# Endstops.net
KiCad netlist of a schematic drawn in Altium Designer
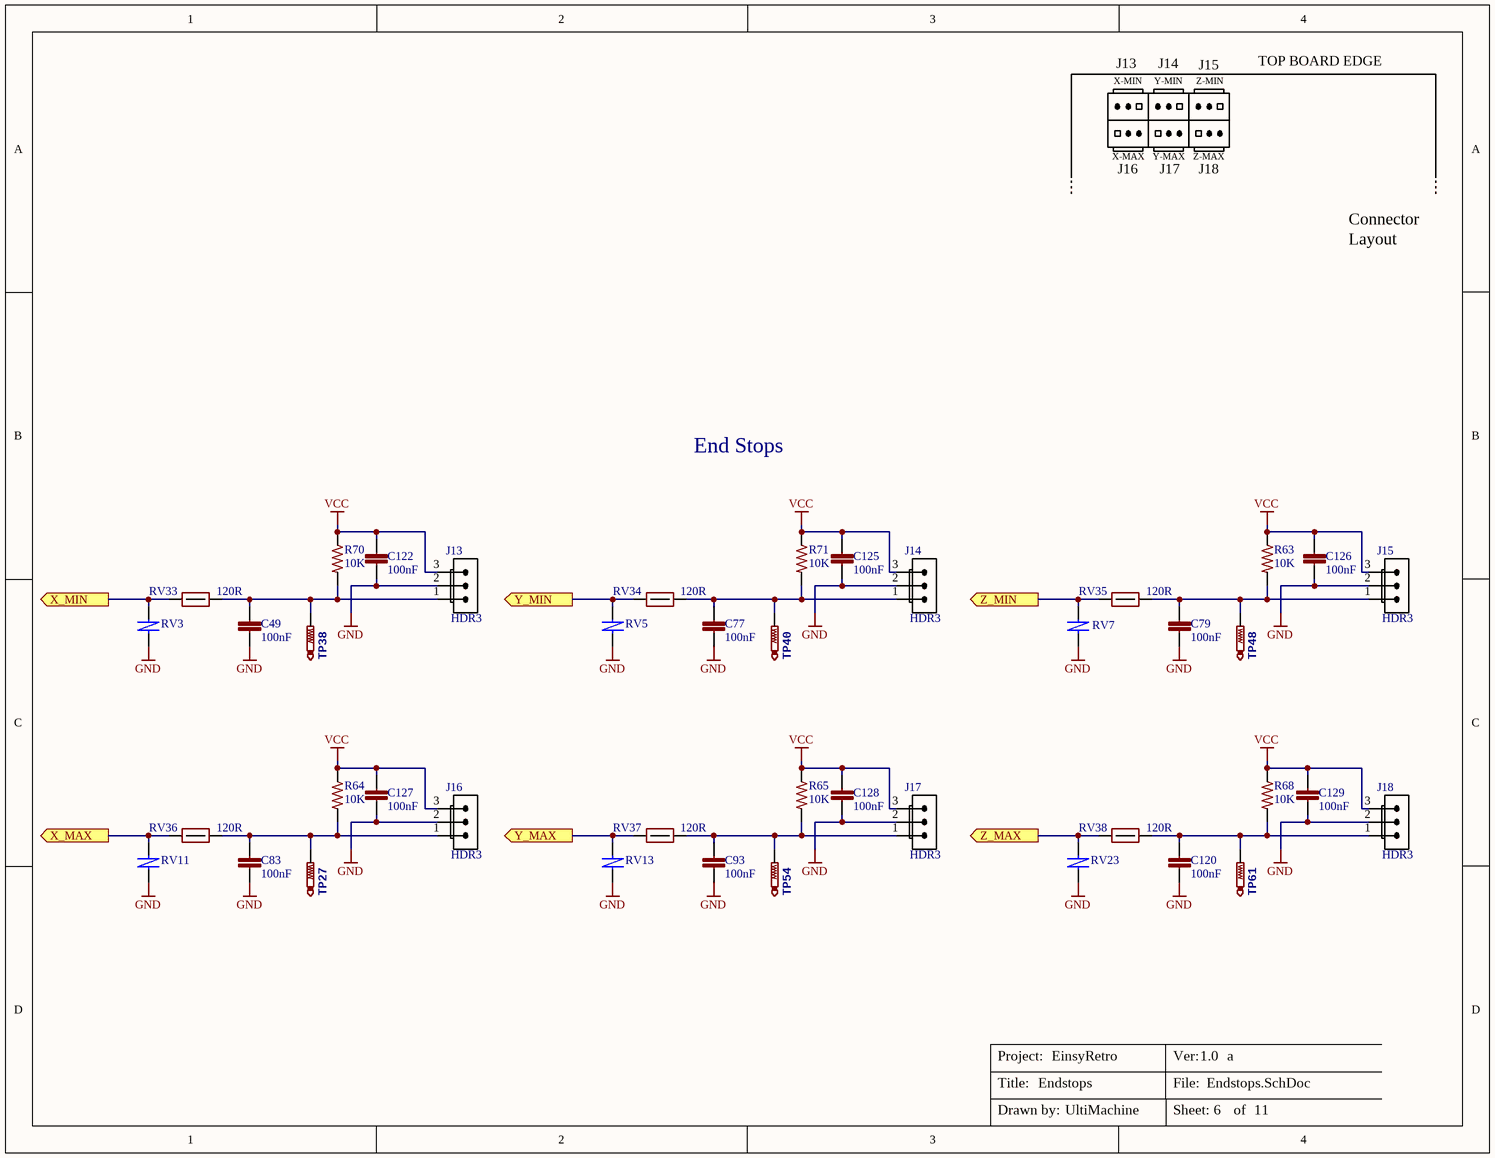
[diagram p0: Endstops.SchDoc]

(export (version "E")
  (design (tool "Eeschema 10.0.6"))
  (components
    (comp (ref "C49")
      (value "100nF")
      (footprint "C0402")
      (description "CAP CER 0402 100nF 16V 10% X7R")
      (fields (field (name "MANUFACTURER") "Murata") (field (name "TOLERANCE") "+/- 10%"))
      (libsource (lib "3Delight") (part "GRM155R71C104KA88D"))
    )
    (comp (ref "C77")
      (value "100nF")
      (footprint "C0402")
      (description "CAP CER 0402 100nF 16V 10% X7R")
      (fields (field (name "MANUFACTURER") "Murata") (field (name "TOLERANCE") "+/- 10%"))
      (libsource (lib "3Delight") (part "GRM155R71C104KA88D"))
    )
    (comp (ref "C79")
      (value "100nF")
      (footprint "C0402")
      (description "CAP CER 0402 100nF 16V 10% X7R")
      (fields (field (name "MANUFACTURER") "Murata") (field (name "TOLERANCE") "+/- 10%"))
      (libsource (lib "3Delight") (part "GRM155R71C104KA88D"))
    )
    (comp (ref "C83")
      (value "100nF")
      (footprint "C0402")
      (description "CAP CER 0402 100nF 16V 10% X7R")
      (fields (field (name "MANUFACTURER") "Murata") (field (name "TOLERANCE") "+/- 10%"))
      (libsource (lib "3Delight") (part "GRM155R71C104KA88D"))
    )
    (comp (ref "C93")
      (value "100nF")
      (footprint "C0402")
      (description "CAP CER 0402 100nF 16V 10% X7R")
      (fields (field (name "MANUFACTURER") "Murata") (field (name "TOLERANCE") "+/- 10%"))
      (libsource (lib "3Delight") (part "GRM155R71C104KA88D"))
    )
    (comp (ref "C120")
      (value "100nF")
      (footprint "C0402")
      (description "CAP CER 0402 100nF 16V 10% X7R")
      (fields (field (name "MANUFACTURER") "Murata") (field (name "TOLERANCE") "+/- 10%"))
      (libsource (lib "3Delight") (part "GRM155R71C104KA88D"))
    )
    (comp (ref "C122")
      (value "100nF")
      (footprint "C0402")
      (description "CAP CER 0402 100nF 16V 10% X7R")
      (fields (field (name "MANUFACTURER") "Murata") (field (name "TOLERANCE") "+/- 10%"))
      (libsource (lib "3Delight") (part "GRM155R71C104KA88D"))
    )
    (comp (ref "C125")
      (value "100nF")
      (footprint "C0402")
      (description "CAP CER 0402 100nF 16V 10% X7R")
      (fields (field (name "MANUFACTURER") "Murata") (field (name "TOLERANCE") "+/- 10%"))
      (libsource (lib "3Delight") (part "GRM155R71C104KA88D"))
    )
    (comp (ref "C126")
      (value "100nF")
      (footprint "C0402")
      (description "CAP CER 0402 100nF 16V 10% X7R")
      (fields (field (name "MANUFACTURER") "Murata") (field (name "TOLERANCE") "+/- 10%"))
      (libsource (lib "3Delight") (part "GRM155R71C104KA88D"))
    )
    (comp (ref "C127")
      (value "100nF")
      (footprint "C0402")
      (description "CAP CER 0402 100nF 16V 10% X7R")
      (fields (field (name "MANUFACTURER") "Murata") (field (name "TOLERANCE") "+/- 10%"))
      (libsource (lib "3Delight") (part "GRM155R71C104KA88D"))
    )
    (comp (ref "C128")
      (value "100nF")
      (footprint "C0402")
      (description "CAP CER 0402 100nF 16V 10% X7R")
      (fields (field (name "MANUFACTURER") "Murata") (field (name "TOLERANCE") "+/- 10%"))
      (libsource (lib "3Delight") (part "GRM155R71C104KA88D"))
    )
    (comp (ref "C129")
      (value "100nF")
      (footprint "C0402")
      (description "CAP CER 0402 100nF 16V 10% X7R")
      (fields (field (name "MANUFACTURER") "Murata") (field (name "TOLERANCE") "+/- 10%"))
      (libsource (lib "3Delight") (part "GRM155R71C104KA88D"))
    )
    (comp (ref "J13")
      (value "HDR3")
      (footprint "70543-03")
      (description "3 Positions Header, Shrouded Connector 0.100\" (2.54mm) Through Hole Gold")
      (fields (field (name "MANUFACTURER") "Molex") (field (name "PART") "3 Pin Conn VERT"))
      (libsource (lib "Archim_0.4") (part "CONN 3POS VERT 0.1{dblquote} SHRD LOCKING"))
    )
    (comp (ref "J14")
      (value "HDR3")
      (footprint "70543-03")
      (description "3 Positions Header, Shrouded Connector 0.100\" (2.54mm) Through Hole Gold")
      (fields (field (name "MANUFACTURER") "Molex") (field (name "PART") "3 Pin Conn VERT"))
      (libsource (lib "Archim_0.4") (part "CONN 3POS VERT 0.1{dblquote} SHRD LOCKING"))
    )
    (comp (ref "J15")
      (value "HDR3")
      (footprint "70543-03")
      (description "3 Positions Header, Shrouded Connector 0.100\" (2.54mm) Through Hole Gold")
      (fields (field (name "MANUFACTURER") "Molex") (field (name "PART") "3 Pin Conn VERT"))
      (libsource (lib "Archim_0.4") (part "CONN 3POS VERT 0.1{dblquote} SHRD LOCKING"))
    )
    (comp (ref "J16")
      (value "HDR3")
      (footprint "70543-03")
      (description "3 Positions Header, Shrouded Connector 0.100\" (2.54mm) Through Hole Gold")
      (fields (field (name "MANUFACTURER") "Molex") (field (name "PART") "3 Pin Conn VERT"))
      (libsource (lib "Archim_0.4") (part "CONN 3POS VERT 0.1{dblquote} SHRD LOCKING"))
    )
    (comp (ref "J17")
      (value "HDR3")
      (footprint "70543-03")
      (description "3 Positions Header, Shrouded Connector 0.100\" (2.54mm) Through Hole Gold")
      (fields (field (name "MANUFACTURER") "Molex") (field (name "PART") "3 Pin Conn VERT"))
      (libsource (lib "Archim_0.4") (part "CONN 3POS VERT 0.1{dblquote} SHRD LOCKING"))
    )
    (comp (ref "J18")
      (value "HDR3")
      (footprint "70543-03")
      (description "3 Positions Header, Shrouded Connector 0.100\" (2.54mm) Through Hole Gold")
      (fields (field (name "MANUFACTURER") "Molex") (field (name "PART") "3 Pin Conn VERT"))
      (libsource (lib "Archim_0.4") (part "CONN 3POS VERT 0.1{dblquote} SHRD LOCKING"))
    )
    (comp (ref "R63")
      (value "10K")
      (footprint "R0402")
      (description "RES SMD 10K OHM 1% 1/16W 0402")
      (fields (field (name "MANUFACTURER") "Yageo") (field (name "PART") "10k 1% 0402"))
      (libsource (lib "3Delight") (part "RC0402FR-0710KP"))
    )
    (comp (ref "R64")
      (value "10K")
      (footprint "R0402")
      (description "RES SMD 10K OHM 1% 1/16W 0402")
      (fields (field (name "MANUFACTURER") "Yageo") (field (name "PART") "10k 1% 0402"))
      (libsource (lib "3Delight") (part "RC0402FR-0710KP"))
    )
    (comp (ref "R65")
      (value "10K")
      (footprint "R0402")
      (description "RES SMD 10K OHM 1% 1/16W 0402")
      (fields (field (name "MANUFACTURER") "Yageo") (field (name "PART") "10k 1% 0402"))
      (libsource (lib "3Delight") (part "RC0402FR-0710KP"))
    )
    (comp (ref "R68")
      (value "10K")
      (footprint "R0402")
      (description "RES SMD 10K OHM 1% 1/16W 0402")
      (fields (field (name "MANUFACTURER") "Yageo") (field (name "PART") "10k 1% 0402"))
      (libsource (lib "3Delight") (part "RC0402FR-0710KP"))
    )
    (comp (ref "R70")
      (value "10K")
      (footprint "R0402")
      (description "RES SMD 10K OHM 1% 1/16W 0402")
      (fields (field (name "MANUFACTURER") "Yageo") (field (name "PART") "10k 1% 0402"))
      (libsource (lib "3Delight") (part "RC0402FR-0710KP"))
    )
    (comp (ref "R71")
      (value "10K")
      (footprint "R0402")
      (description "RES SMD 10K OHM 1% 1/16W 0402")
      (fields (field (name "MANUFACTURER") "Yageo") (field (name "PART") "10k 1% 0402"))
      (libsource (lib "3Delight") (part "RC0402FR-0710KP"))
    )
    (comp (ref "RV3")
      (value "VRS0402SR55R101N")
      (footprint "C0402")
      (description "Multi-Layer Varistor")
      (fields (field (name "MANUFACTURER") "Yageo") (field (name "PART") "12V"))
      (libsource (lib "3Delight") (part "VRS0402SR55R101N"))
    )
    (comp (ref "RV5")
      (value "VRS0402SR55R101N")
      (footprint "C0402")
      (description "Multi-Layer Varistor")
      (fields (field (name "MANUFACTURER") "Yageo") (field (name "PART") "12V"))
      (libsource (lib "3Delight") (part "VRS0402SR55R101N"))
    )
    (comp (ref "RV7")
      (value "VRS0402SR55R101N")
      (footprint "C0402")
      (description "Multi-Layer Varistor")
      (fields (field (name "MANUFACTURER") "Yageo") (field (name "PART") "12V"))
      (libsource (lib "3Delight") (part "VRS0402SR55R101N"))
    )
    (comp (ref "RV11")
      (value "VRS0402SR55R101N")
      (footprint "C0402")
      (description "Multi-Layer Varistor")
      (fields (field (name "MANUFACTURER") "Yageo") (field (name "PART") "12V"))
      (libsource (lib "3Delight") (part "VRS0402SR55R101N"))
    )
    (comp (ref "RV13")
      (value "VRS0402SR55R101N")
      (footprint "C0402")
      (description "Multi-Layer Varistor")
      (fields (field (name "MANUFACTURER") "Yageo") (field (name "PART") "12V"))
      (libsource (lib "3Delight") (part "VRS0402SR55R101N"))
    )
    (comp (ref "RV23")
      (value "VRS0402SR55R101N")
      (footprint "C0402")
      (description "Multi-Layer Varistor")
      (fields (field (name "MANUFACTURER") "Yageo") (field (name "PART") "12V"))
      (libsource (lib "3Delight") (part "VRS0402SR55R101N"))
    )
    (comp (ref "RV33")
      (value "120R")
      (footprint "R0402")
      (description "FERRITE BEAD 120 OHM 0402 1LN")
      (fields (field (name "MANUFACTURER") "Taiyo Yuden") (field (name "PART") "FERRITE 120R 1A 0402"))
      (libsource (lib "Inductors") (part "FERRITE 120R 1A 0402"))
    )
    (comp (ref "RV34")
      (value "120R")
      (footprint "R0402")
      (description "FERRITE BEAD 120 OHM 0402 1LN")
      (fields (field (name "MANUFACTURER") "Taiyo Yuden") (field (name "PART") "FERRITE 120R 1A 0402"))
      (libsource (lib "Inductors") (part "FERRITE 120R 1A 0402"))
    )
    (comp (ref "RV35")
      (value "120R")
      (footprint "R0402")
      (description "FERRITE BEAD 120 OHM 0402 1LN")
      (fields (field (name "MANUFACTURER") "Taiyo Yuden") (field (name "PART") "FERRITE 120R 1A 0402"))
      (libsource (lib "Inductors") (part "FERRITE 120R 1A 0402"))
    )
    (comp (ref "RV36")
      (value "120R")
      (footprint "R0402")
      (description "FERRITE BEAD 120 OHM 0402 1LN")
      (fields (field (name "MANUFACTURER") "Taiyo Yuden") (field (name "PART") "FERRITE 120R 1A 0402"))
      (libsource (lib "Inductors") (part "FERRITE 120R 1A 0402"))
    )
    (comp (ref "RV37")
      (value "120R")
      (footprint "R0402")
      (description "FERRITE BEAD 120 OHM 0402 1LN")
      (fields (field (name "MANUFACTURER") "Taiyo Yuden") (field (name "PART") "FERRITE 120R 1A 0402"))
      (libsource (lib "Inductors") (part "FERRITE 120R 1A 0402"))
    )
    (comp (ref "RV38")
      (value "120R")
      (footprint "R0402")
      (description "FERRITE BEAD 120 OHM 0402 1LN")
      (fields (field (name "MANUFACTURER") "Taiyo Yuden") (field (name "PART") "FERRITE 120R 1A 0402"))
      (libsource (lib "Inductors") (part "FERRITE 120R 1A 0402"))
    )
    (comp (ref "TP27")
      (value "TestPoint")
      (footprint "TP1-27")
      (description "Test Point")
      (libsource (lib "3Delight") (part "TestPoint"))
    )
    (comp (ref "TP38")
      (value "TestPoint")
      (footprint "TP1-27")
      (description "Test Point")
      (libsource (lib "3Delight") (part "TestPoint"))
    )
    (comp (ref "TP40")
      (value "TestPoint")
      (footprint "TP1-27")
      (description "Test Point")
      (libsource (lib "3Delight") (part "TestPoint"))
    )
    (comp (ref "TP48")
      (value "TestPoint")
      (footprint "TP1-27")
      (description "Test Point")
      (libsource (lib "3Delight") (part "TestPoint"))
    )
    (comp (ref "TP54")
      (value "TestPoint")
      (footprint "TP1-27")
      (description "Test Point")
      (libsource (lib "3Delight") (part "TestPoint"))
    )
    (comp (ref "TP61")
      (value "TestPoint")
      (footprint "TP1-27")
      (description "Test Point")
      (libsource (lib "3Delight") (part "TestPoint"))
    )
  )
  (nets
    (net (code "1") (name "/X_MAX") (class "Default")
      (node (ref "RV11") (pin "2") (pinfunction "2_2") (pintype "passive"))
      (node (ref "RV36") (pin "1") (pinfunction "1_1") (pintype "passive"))
    )
    (net (code "2") (name "/X_MIN") (class "Default")
      (node (ref "RV3") (pin "2") (pinfunction "2_2") (pintype "passive"))
      (node (ref "RV33") (pin "1") (pinfunction "1_1") (pintype "passive"))
    )
    (net (code "3") (name "/Y_MAX") (class "Default")
      (node (ref "RV13") (pin "2") (pinfunction "2_2") (pintype "passive"))
      (node (ref "RV37") (pin "1") (pinfunction "1_1") (pintype "passive"))
    )
    (net (code "4") (name "/Y_MIN") (class "Default")
      (node (ref "RV34") (pin "1") (pinfunction "1_1") (pintype "passive"))
      (node (ref "RV5") (pin "2") (pinfunction "2_2") (pintype "passive"))
    )
    (net (code "5") (name "/Z_MAX") (class "Default")
      (node (ref "RV23") (pin "2") (pinfunction "2_2") (pintype "passive"))
      (node (ref "RV38") (pin "1") (pinfunction "1_1") (pintype "passive"))
    )
    (net (code "6") (name "/Z_MIN") (class "Default")
      (node (ref "RV35") (pin "1") (pinfunction "1_1") (pintype "passive"))
      (node (ref "RV7") (pin "2") (pinfunction "2_2") (pintype "passive"))
    )
    (net (code "7") (name "GND") (class "Default")
      (node (ref "C120") (pin "2") (pinfunction "2_2") (pintype "passive"))
      (node (ref "C122") (pin "2") (pinfunction "2_2") (pintype "passive"))
      (node (ref "C125") (pin "2") (pinfunction "2_2") (pintype "passive"))
      (node (ref "C126") (pin "2") (pinfunction "2_2") (pintype "passive"))
      (node (ref "C127") (pin "2") (pinfunction "2_2") (pintype "passive"))
      (node (ref "C128") (pin "2") (pinfunction "2_2") (pintype "passive"))
      (node (ref "C129") (pin "2") (pinfunction "2_2") (pintype "passive"))
      (node (ref "C49") (pin "2") (pinfunction "2_2") (pintype "passive"))
      (node (ref "C77") (pin "2") (pinfunction "2_2") (pintype "passive"))
      (node (ref "C79") (pin "2") (pinfunction "2_2") (pintype "passive"))
      (node (ref "C83") (pin "2") (pinfunction "2_2") (pintype "passive"))
      (node (ref "C93") (pin "2") (pinfunction "2_2") (pintype "passive"))
      (node (ref "J13") (pin "2") (pinfunction "S_2") (pintype "passive"))
      (node (ref "J14") (pin "2") (pinfunction "S_2") (pintype "passive"))
      (node (ref "J15") (pin "2") (pinfunction "S_2") (pintype "passive"))
      (node (ref "J16") (pin "2") (pinfunction "S_2") (pintype "passive"))
      (node (ref "J17") (pin "2") (pinfunction "S_2") (pintype "passive"))
      (node (ref "J18") (pin "2") (pinfunction "S_2") (pintype "passive"))
      (node (ref "RV11") (pin "1") (pinfunction "1_1") (pintype "passive"))
      (node (ref "RV13") (pin "1") (pinfunction "1_1") (pintype "passive"))
      (node (ref "RV23") (pin "1") (pinfunction "1_1") (pintype "passive"))
      (node (ref "RV3") (pin "1") (pinfunction "1_1") (pintype "passive"))
      (node (ref "RV5") (pin "1") (pinfunction "1_1") (pintype "passive"))
      (node (ref "RV7") (pin "1") (pinfunction "1_1") (pintype "passive"))
    )
    (net (code "8") (name "Net-(C49-Pad1)") (class "Default")
      (node (ref "C49") (pin "1") (pinfunction "1_1") (pintype "passive"))
      (node (ref "J13") (pin "1") (pinfunction "S_1") (pintype "passive"))
      (node (ref "R70") (pin "2") (pinfunction "2_2") (pintype "passive"))
      (node (ref "RV33") (pin "2") (pinfunction "2_2") (pintype "passive"))
      (node (ref "TP38") (pin "TP") (pinfunction "TP_TP") (pintype "passive"))
    )
    (net (code "9") (name "Net-(C77-Pad1)") (class "Default")
      (node (ref "C77") (pin "1") (pinfunction "1_1") (pintype "passive"))
      (node (ref "J14") (pin "1") (pinfunction "S_1") (pintype "passive"))
      (node (ref "R71") (pin "2") (pinfunction "2_2") (pintype "passive"))
      (node (ref "RV34") (pin "2") (pinfunction "2_2") (pintype "passive"))
      (node (ref "TP40") (pin "TP") (pinfunction "TP_TP") (pintype "passive"))
    )
    (net (code "10") (name "Net-(C79-Pad1)") (class "Default")
      (node (ref "C79") (pin "1") (pinfunction "1_1") (pintype "passive"))
      (node (ref "J15") (pin "1") (pinfunction "S_1") (pintype "passive"))
      (node (ref "R63") (pin "2") (pinfunction "2_2") (pintype "passive"))
      (node (ref "RV35") (pin "2") (pinfunction "2_2") (pintype "passive"))
      (node (ref "TP48") (pin "TP") (pinfunction "TP_TP") (pintype "passive"))
    )
    (net (code "11") (name "Net-(C83-Pad1)") (class "Default")
      (node (ref "C83") (pin "1") (pinfunction "1_1") (pintype "passive"))
      (node (ref "J16") (pin "1") (pinfunction "S_1") (pintype "passive"))
      (node (ref "R64") (pin "2") (pinfunction "2_2") (pintype "passive"))
      (node (ref "RV36") (pin "2") (pinfunction "2_2") (pintype "passive"))
      (node (ref "TP27") (pin "TP") (pinfunction "TP_TP") (pintype "passive"))
    )
    (net (code "12") (name "Net-(C93-Pad1)") (class "Default")
      (node (ref "C93") (pin "1") (pinfunction "1_1") (pintype "passive"))
      (node (ref "J17") (pin "1") (pinfunction "S_1") (pintype "passive"))
      (node (ref "R65") (pin "2") (pinfunction "2_2") (pintype "passive"))
      (node (ref "RV37") (pin "2") (pinfunction "2_2") (pintype "passive"))
      (node (ref "TP54") (pin "TP") (pinfunction "TP_TP") (pintype "passive"))
    )
    (net (code "13") (name "Net-(C120-Pad1)") (class "Default")
      (node (ref "C120") (pin "1") (pinfunction "1_1") (pintype "passive"))
      (node (ref "J18") (pin "1") (pinfunction "S_1") (pintype "passive"))
      (node (ref "R68") (pin "2") (pinfunction "2_2") (pintype "passive"))
      (node (ref "RV38") (pin "2") (pinfunction "2_2") (pintype "passive"))
      (node (ref "TP61") (pin "TP") (pinfunction "TP_TP") (pintype "passive"))
    )
    (net (code "14") (name "VCC") (class "Default")
      (node (ref "C122") (pin "1") (pinfunction "1_1") (pintype "passive"))
      (node (ref "C125") (pin "1") (pinfunction "1_1") (pintype "passive"))
      (node (ref "C126") (pin "1") (pinfunction "1_1") (pintype "passive"))
      (node (ref "C127") (pin "1") (pinfunction "1_1") (pintype "passive"))
      (node (ref "C128") (pin "1") (pinfunction "1_1") (pintype "passive"))
      (node (ref "C129") (pin "1") (pinfunction "1_1") (pintype "passive"))
      (node (ref "J13") (pin "3") (pinfunction "S_3") (pintype "passive"))
      (node (ref "J14") (pin "3") (pinfunction "S_3") (pintype "passive"))
      (node (ref "J15") (pin "3") (pinfunction "S_3") (pintype "passive"))
      (node (ref "J16") (pin "3") (pinfunction "S_3") (pintype "passive"))
      (node (ref "J17") (pin "3") (pinfunction "S_3") (pintype "passive"))
      (node (ref "J18") (pin "3") (pinfunction "S_3") (pintype "passive"))
      (node (ref "R63") (pin "1") (pinfunction "1_1") (pintype "passive"))
      (node (ref "R64") (pin "1") (pinfunction "1_1") (pintype "passive"))
      (node (ref "R65") (pin "1") (pinfunction "1_1") (pintype "passive"))
      (node (ref "R68") (pin "1") (pinfunction "1_1") (pintype "passive"))
      (node (ref "R70") (pin "1") (pinfunction "1_1") (pintype "passive"))
      (node (ref "R71") (pin "1") (pinfunction "1_1") (pintype "passive"))
    )
  )
)
